# Cell4_Balancing.net
KiCad netlist of a schematic drawn in Altium Designer
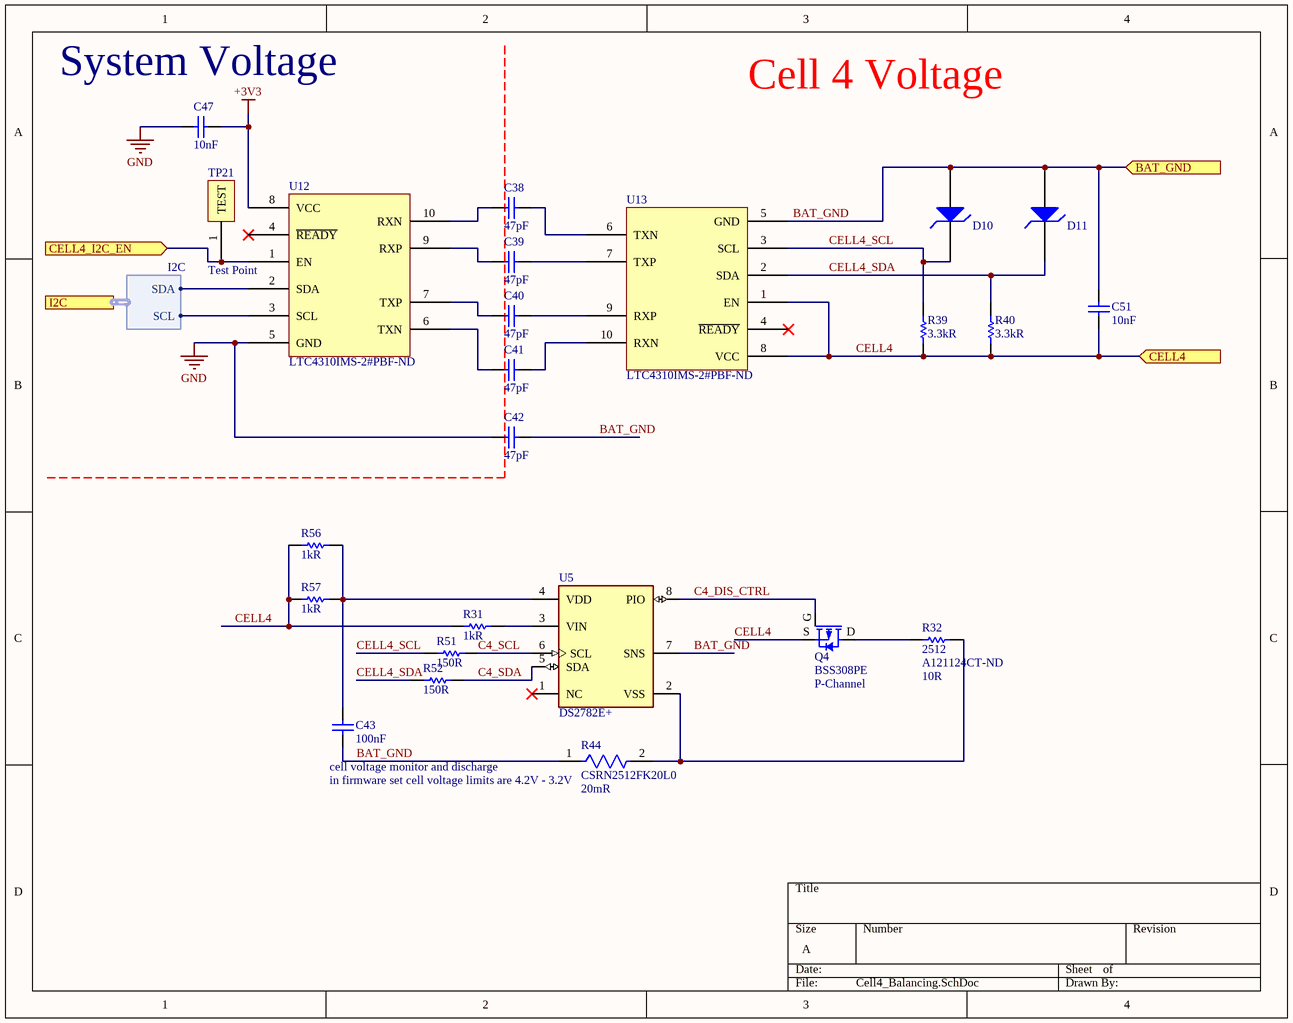
[diagram p0: Cell4_Balancing.SchDoc]

(export (version "E")
  (design (tool "Eeschema 10.0.6"))
  (components
    (comp (ref "C38")
      (value "06031A470FAT2A")
      (footprint "CAPC1608X90X35ML15T15")
      (fields (field (name "MANUFACTURER") "AVX Interconnect / Elco") (field (name "CAPACITANCE") "47pF"))
      (libsource (lib "Altium Content Vault") (part "CAP"))
    )
    (comp (ref "C39")
      (value "06031A470FAT2A")
      (footprint "CAPC1608X90X35ML15T15")
      (fields (field (name "MANUFACTURER") "AVX Interconnect / Elco") (field (name "CAPACITANCE") "47pF"))
      (libsource (lib "Altium Content Vault") (part "CAP"))
    )
    (comp (ref "C40")
      (value "06031A470FAT2A")
      (footprint "CAPC1608X90X35ML15T15")
      (fields (field (name "MANUFACTURER") "AVX Interconnect / Elco") (field (name "CAPACITANCE") "47pF"))
      (libsource (lib "Altium Content Vault") (part "CAP"))
    )
    (comp (ref "C41")
      (value "06031A470FAT2A")
      (footprint "CAPC1608X90X35ML15T15")
      (fields (field (name "MANUFACTURER") "AVX Interconnect / Elco") (field (name "CAPACITANCE") "47pF"))
      (libsource (lib "Altium Content Vault") (part "CAP"))
    )
    (comp (ref "C42")
      (value "06031A470FAT2A")
      (footprint "CAPC1608X90X35ML15T15")
      (fields (field (name "MANUFACTURER") "AVX Interconnect / Elco") (field (name "CAPACITANCE") "47pF"))
      (libsource (lib "Altium Content Vault") (part "CAP"))
    )
    (comp (ref "C43")
      (value "Capacitor 0402")
      (footprint "C0402")
      (description "CAP CER 0.1UF 25V X5R 0402 / High Value Multilayer Ceramic Capacitors (High dielectric type)")
      (fields
        (field (name "MANUFACTURER") "Taiyo Yuden")
        (field (name "MANUFACTURER PART NUMBER") "TMK105BJ104KV-F")
        (field (name "CAPACITANCE") "100nF")
      )
      (libsource (lib "Wally_BMS") (part "Capacitor 0402"))
    )
    (comp (ref "C47")
      (value "Capacitor 0402")
      (footprint "C0402")
      (description "Cap Ceramic 0.01uF 25V X7R 10% Pad SMD 0402 125C T/R")
      (fields
        (field (name "MANUFACTURER") "Samsung")
        (field (name "MANUFACTURER PART NUMBER") "CL05B103KA5NNNC")
        (field (name "CAPACITANCE") "10nF")
      )
      (libsource (lib "Wally_BMS") (part "Capacitor 0402"))
    )
    (comp (ref "C51")
      (value "Capacitor 0402")
      (footprint "C0402")
      (description "Cap Ceramic 0.01uF 25V X7R 10% Pad SMD 0402 125C T/R")
      (fields
        (field (name "MANUFACTURER") "Samsung")
        (field (name "MANUFACTURER PART NUMBER") "CL05B103KA5NNNC")
        (field (name "CAPACITANCE") "10nF")
      )
      (libsource (lib "Wally_BMS") (part "Capacitor 0402"))
    )
    (comp (ref "D10")
      (value "BZT52C4V7LP-7")
      (footprint "bzt52c4v7lp-7")
      (description "BZT52C4V7LP Series 4.7 V 10 mA Surface Mount Zener Diode - DFN1006-2")
      (fields (field (name "MANUFACTURER") "Diodes") (field (name "TOLERANCE") "6%"))
      (libsource (lib "Wally_BMS") (part "BZT52C4V7LP-7"))
    )
    (comp (ref "D11")
      (value "BZT52C4V7LP-7")
      (footprint "bzt52c4v7lp-7")
      (description "BZT52C4V7LP Series 4.7 V 10 mA Surface Mount Zener Diode - DFN1006-2")
      (fields (field (name "MANUFACTURER") "Diodes") (field (name "TOLERANCE") "6%"))
      (libsource (lib "Wally_BMS") (part "BZT52C4V7LP-7"))
    )
    (comp (ref "Q4")
      (value "BSS308PE")
      (footprint "BSS308PE")
      (description "MOSFET P-CH 30V 2A SOT23")
      (fields (field (name "FET TYPE") "P-Channel"))
      (libsource (lib "Transistors") (part "BSS308PE"))
    )
    (comp (ref "R31")
      (value "Resistor 0402")
      (footprint "RES0402")
      (description "Res Thick Film 0402 1K Ohm 1% 0.063W(1/16W) ±100ppm/C Pad SMD Automotive T/R")
      (fields
        (field (name "MANUFACTURER") "Stackpole Electronics")
        (field (name "MANUFACTURER PART NUMBER") "RMCF0402FT1K00")
        (field (name "RESISTANCE") "1kR")
      )
      (libsource (lib "Wally_BMS") (part "Resistor 0402"))
    )
    (comp (ref "R32")
      (value "Resistor 2512")
      (footprint "RES2512")
      (fields
        (field (name "PACKAGE / CASE") "2512")
        (field (name "SUPPLIER PART NUMBER 1") "A121124CT-ND")
        (field (name "MANUFACTURER") "TE Connectivity CGS")
        (field (name "MANUFACTURER PART NUMBER") "1-2176230-4")
        (field (name "RESISTANCE") "10R")
        (field (name "TOLERANCE") "5%")
      )
      (libsource (lib "Wally_BMS") (part "Resistor 2512"))
    )
    (comp (ref "R39")
      (value "Resistor 0402")
      (footprint "RES0402")
      (description "Res Thin Film 0402 3.3K Ohm 1% 1/16W ±50ppm/°C Molded SMD SMD Paper T/R")
      (fields
        (field (name "MANUFACTURER") "Yageo")
        (field (name "MANUFACTURER PART NUMBER") "RT0402FRE073K3L")
        (field (name "RESISTANCE") "3.3kR")
      )
      (libsource (lib "Wally_BMS") (part "Resistor 0402"))
    )
    (comp (ref "R40")
      (value "Resistor 0402")
      (footprint "RES0402")
      (description "Res Thin Film 0402 3.3K Ohm 1% 1/16W ±50ppm/°C Molded SMD SMD Paper T/R")
      (fields
        (field (name "MANUFACTURER") "Yageo")
        (field (name "MANUFACTURER PART NUMBER") "RT0402FRE073K3L")
        (field (name "RESISTANCE") "3.3kR")
      )
      (libsource (lib "Wally_BMS") (part "Resistor 0402"))
    )
    (comp (ref "R44")
      (value "CSRN2512FK20L0")
      (footprint "FP-CSRN2512-IPC_C")
      (description "Res Thick Film 2512 20mΩ 1% 2W ±200ppm/°C Molded SMD Plastic T/R")
      (fields (field (name "RESISTANCE") "20mR") (field (name "TOLERANCE") "1%"))
      (libsource (lib "Altium Content Vault") (part "1029c3af85768c4190bb7ad29bc67b5"))
    )
    (comp (ref "R51")
      (value "Resistor 0402")
      (footprint "RES0402")
      (description "Res Thin Film 0402 150 Ohm 1% 1/16W ±50ppm/°C Molded SMD SMD Paper T/R")
      (fields
        (field (name "MANUFACTURER") "Yageo")
        (field (name "MANUFACTURER PART NUMBER") "RT0402FRE07150RL")
        (field (name "RESISTANCE") "150R")
      )
      (libsource (lib "Wally_BMS") (part "Resistor 0402"))
    )
    (comp (ref "R52")
      (value "Resistor 0402")
      (footprint "RES0402")
      (description "Res Thin Film 0402 150 Ohm 1% 1/16W ±50ppm/°C Molded SMD SMD Paper T/R")
      (fields
        (field (name "MANUFACTURER") "Yageo")
        (field (name "MANUFACTURER PART NUMBER") "RT0402FRE07150RL")
        (field (name "RESISTANCE") "150R")
      )
      (libsource (lib "Wally_BMS") (part "Resistor 0402"))
    )
    (comp (ref "R56")
      (value "Resistor 0402")
      (footprint "RES0402")
      (description "Res Thick Film 0402 1K Ohm 1% 0.063W(1/16W) ±100ppm/C Pad SMD Automotive T/R")
      (fields
        (field (name "MANUFACTURER") "Stackpole Electronics")
        (field (name "MANUFACTURER PART NUMBER") "RMCF0402FT1K00")
        (field (name "RESISTANCE") "1kR")
      )
      (libsource (lib "Wally_BMS") (part "Resistor 0402"))
    )
    (comp (ref "R57")
      (value "Resistor 0402")
      (footprint "RES0402")
      (description "Res Thick Film 0402 1K Ohm 1% 0.063W(1/16W) ±100ppm/C Pad SMD Automotive T/R")
      (fields
        (field (name "MANUFACTURER") "Stackpole Electronics")
        (field (name "MANUFACTURER PART NUMBER") "RMCF0402FT1K00")
        (field (name "RESISTANCE") "1kR")
      )
      (libsource (lib "Wally_BMS") (part "Resistor 0402"))
    )
    (comp (ref "TP21")
      (value "Test Point")
      (footprint "TEST POINT")
      (libsource (lib "Wally_BMS") (part "Test Point"))
    )
    (comp (ref "U5")
      (value "DS2782E+")
      (footprint "FP-H8-2-MFG")
      (description "IC FUEL GAUGE BATT 8TSSOP")
      (fields
        (field (name "OCTOPART") "https://octopart.com/ds2782e%2B-maxim+integrated-8045252")
        (field (name "MANUFACTURER") "Maxim")
      )
      (libsource (lib "Altium Content Vault") (part "f9098ddd067e7739cd521d50be25c58"))
    )
    (comp (ref "U12")
      (value "LTC4310IMS-2#PBF-ND")
      (footprint "MSOP-10_MS_LIT")
      (description "DIGITAL ISOLATOR 2CH I2C 10MSOP")
      (libsource (lib "") (part "LTC4310IMS-2#PBF_1"))
    )
    (comp (ref "U13")
      (value "LTC4310IMS-2#PBF-ND")
      (footprint "MSOP-10_MS_LIT")
      (description "DIGITAL ISOLATOR 2CH I2C 10MSOP")
      (libsource (lib "Wally_BMS") (part "LTC4310IMS-2#PBF"))
    )
  )
  (nets
    (net (code "2") (name "+3V3") (class "Default")
      (node (ref "C47") (pin "1") (pinfunction "1_1") (pintype "passive"))
      (node (ref "U12") (pin "8") (pinfunction "VCC_8") (pintype "passive"))
    )
    (net (code "3") (name "/BAT_GND") (class "Default")
      (node (ref "C42") (pin "2") (pinfunction "2_2") (pintype "passive"))
      (node (ref "C43") (pin "1") (pinfunction "1_1") (pintype "passive"))
      (node (ref "C51") (pin "1") (pinfunction "1_1") (pintype "passive"))
      (node (ref "D10") (pin "2") (pinfunction "A_2") (pintype "passive"))
      (node (ref "D11") (pin "2") (pinfunction "A_2") (pintype "passive"))
      (node (ref "R44") (pin "1") (pinfunction "1_1") (pintype "passive"))
      (node (ref "U13") (pin "5") (pinfunction "GND_5") (pintype "passive"))
      (node (ref "U5") (pin "7") (pinfunction "SNS_7") (pintype "passive"))
    )
    (net (code "4") (name "/C4_DIS_CTRL") (class "Default")
      (node (ref "Q4") (pin "G") (pinfunction "G_G") (pintype "passive"))
      (node (ref "U5") (pin "8") (pinfunction "PIO_8") (pintype "bidirectional"))
    )
    (net (code "5") (name "/C4_SCL") (class "Default")
      (node (ref "R51") (pin "1") (pinfunction "1_1") (pintype "passive"))
      (node (ref "U5") (pin "6") (pinfunction "SCL_6") (pintype "input"))
    )
    (net (code "6") (name "/C4_SDA") (class "Default")
      (node (ref "R52") (pin "1") (pinfunction "1_1") (pintype "passive"))
      (node (ref "U5") (pin "5") (pinfunction "SDA_5") (pintype "bidirectional"))
    )
    (net (code "7") (name "/CELL4") (class "Default")
      (node (ref "C51") (pin "2") (pinfunction "2_2") (pintype "passive"))
      (node (ref "Q4") (pin "S") (pinfunction "3_S") (pintype "passive"))
      (node (ref "R31") (pin "1") (pinfunction "1_1") (pintype "passive"))
      (node (ref "R39") (pin "1") (pinfunction "1_1") (pintype "passive"))
      (node (ref "R40") (pin "1") (pinfunction "1_1") (pintype "passive"))
      (node (ref "R56") (pin "1") (pinfunction "1_1") (pintype "passive"))
      (node (ref "R57") (pin "1") (pinfunction "1_1") (pintype "passive"))
      (node (ref "U13") (pin "1") (pinfunction "EN_1") (pintype "passive"))
      (node (ref "U13") (pin "8") (pinfunction "VCC_8") (pintype "passive"))
    )
    (net (code "8") (name "/CELL4_I2C_EN") (class "Default")
      (node (ref "TP21") (pin "1") (pinfunction "TEST_1") (pintype "passive"))
      (node (ref "U12") (pin "1") (pinfunction "EN_1") (pintype "passive"))
    )
    (net (code "9") (name "/CELL4_SCL") (class "Default")
      (node (ref "D10") (pin "1") (pinfunction "K_1") (pintype "passive"))
      (node (ref "R39") (pin "2") (pinfunction "2_2") (pintype "passive"))
      (node (ref "R51") (pin "2") (pinfunction "2_2") (pintype "passive"))
      (node (ref "U13") (pin "3") (pinfunction "SCL_3") (pintype "passive"))
    )
    (net (code "10") (name "/CELL4_SDA") (class "Default")
      (node (ref "D11") (pin "1") (pinfunction "K_1") (pintype "passive"))
      (node (ref "R40") (pin "2") (pinfunction "2_2") (pintype "passive"))
      (node (ref "R52") (pin "2") (pinfunction "2_2") (pintype "passive"))
      (node (ref "U13") (pin "2") (pinfunction "SDA_2") (pintype "passive"))
    )
    (net (code "11") (name "/SCL") (class "Default")
      (node (ref "U12") (pin "3") (pinfunction "SCL_3") (pintype "passive"))
    )
    (net (code "12") (name "/SDA") (class "Default")
      (node (ref "U12") (pin "2") (pinfunction "SDA_2") (pintype "passive"))
    )
    (net (code "14") (name "GND") (class "Default")
      (node (ref "C42") (pin "1") (pinfunction "1_1") (pintype "passive"))
      (node (ref "C47") (pin "2") (pinfunction "2_2") (pintype "passive"))
      (node (ref "U12") (pin "5") (pinfunction "GND_5") (pintype "passive"))
    )
    (net (code "15") (name "Net-(Q4-PadD)") (class "Default")
      (node (ref "Q4") (pin "D") (pinfunction "D_D") (pintype "passive"))
      (node (ref "R32") (pin "1") (pinfunction "1_1") (pintype "passive"))
    )
    (net (code "16") (name "Net-(U5-VDD)") (class "Default")
      (node (ref "C43") (pin "2") (pinfunction "2_2") (pintype "passive"))
      (node (ref "R56") (pin "2") (pinfunction "2_2") (pintype "passive"))
      (node (ref "R57") (pin "2") (pinfunction "2_2") (pintype "passive"))
      (node (ref "U5") (pin "4") (pinfunction "VDD_4") (pintype "power_in"))
    )
    (net (code "17") (name "Net-(U5-VIN)") (class "Default")
      (node (ref "R31") (pin "2") (pinfunction "2_2") (pintype "passive"))
      (node (ref "U5") (pin "3") (pinfunction "VIN_3") (pintype "passive"))
    )
    (net (code "18") (name "Net-(U5-VSS)") (class "Default")
      (node (ref "R32") (pin "2") (pinfunction "2_2") (pintype "passive"))
      (node (ref "R44") (pin "2") (pinfunction "2_2") (pintype "passive"))
      (node (ref "U5") (pin "2") (pinfunction "VSS_2") (pintype "power_in"))
    )
    (net (code "19") (name "Net-(U12-RXN)") (class "Default")
      (node (ref "C38") (pin "1") (pinfunction "1_1") (pintype "passive"))
      (node (ref "U12") (pin "10") (pinfunction "RXN_10") (pintype "passive"))
    )
    (net (code "20") (name "Net-(U12-RXP)") (class "Default")
      (node (ref "C39") (pin "1") (pinfunction "1_1") (pintype "passive"))
      (node (ref "U12") (pin "9") (pinfunction "RXP_9") (pintype "passive"))
    )
    (net (code "21") (name "Net-(U12-TXN)") (class "Default")
      (node (ref "C41") (pin "1") (pinfunction "1_1") (pintype "passive"))
      (node (ref "U12") (pin "6") (pinfunction "TXN_6") (pintype "passive"))
    )
    (net (code "22") (name "Net-(U12-TXP)") (class "Default")
      (node (ref "C40") (pin "1") (pinfunction "1_1") (pintype "passive"))
      (node (ref "U12") (pin "7") (pinfunction "TXP_7") (pintype "passive"))
    )
    (net (code "23") (name "Net-(U13-RXN)") (class "Default")
      (node (ref "C41") (pin "2") (pinfunction "2_2") (pintype "passive"))
      (node (ref "U13") (pin "10") (pinfunction "RXN_10") (pintype "passive"))
    )
    (net (code "24") (name "Net-(U13-RXP)") (class "Default")
      (node (ref "C40") (pin "2") (pinfunction "2_2") (pintype "passive"))
      (node (ref "U13") (pin "9") (pinfunction "RXP_9") (pintype "passive"))
    )
    (net (code "25") (name "Net-(U13-TXN)") (class "Default")
      (node (ref "C38") (pin "2") (pinfunction "2_2") (pintype "passive"))
      (node (ref "U13") (pin "6") (pinfunction "TXN_6") (pintype "passive"))
    )
    (net (code "26") (name "Net-(U13-TXP)") (class "Default")
      (node (ref "C39") (pin "2") (pinfunction "2_2") (pintype "passive"))
      (node (ref "U13") (pin "7") (pinfunction "TXP_7") (pintype "passive"))
    )
    (net (code "27") (name "unconnected-(U5-NC-Pad1)") (class "Default")
      (node (ref "U5") (pin "1") (pinfunction "NC_1") (pintype "passive+no_connect"))
    )
    (net (code "28") (name "unconnected-(U12-~{READY}-Pad4)") (class "Default")
      (node (ref "U12") (pin "4") (pinfunction "~{READY}_4") (pintype "passive+no_connect"))
    )
    (net (code "29") (name "unconnected-(U13-~{READY}-Pad4)") (class "Default")
      (node (ref "U13") (pin "4") (pinfunction "~{READY}_4") (pintype "passive+no_connect"))
    )
  )
)
